# Kontakter.net
KiCad netlist of a schematic drawn in Altium Designer
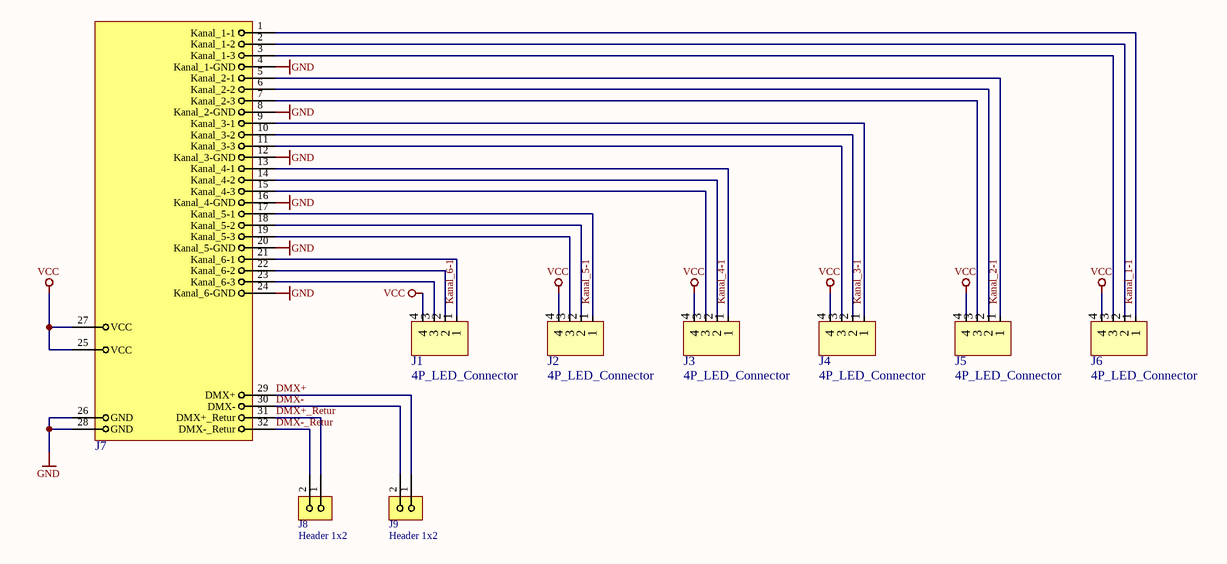
[diagram p0: Kontakter.SchDoc]

(export (version "E")
  (design (tool "Eeschema 10.0.6"))
  (components
    (comp (ref "J1")
      (value "4P_LED_Connector")
      (footprint "LED_solder_connections")
      (libsource (lib "4P_LED_connector") (part "4P_LED_Connector"))
    )
    (comp (ref "J2")
      (value "4P_LED_Connector")
      (footprint "LED_solder_connections")
      (libsource (lib "4P_LED_connector") (part "4P_LED_Connector"))
    )
    (comp (ref "J3")
      (value "4P_LED_Connector")
      (footprint "LED_solder_connections")
      (libsource (lib "4P_LED_connector") (part "4P_LED_Connector"))
    )
    (comp (ref "J4")
      (value "4P_LED_Connector")
      (footprint "LED_solder_connections")
      (libsource (lib "4P_LED_connector") (part "4P_LED_Connector"))
    )
    (comp (ref "J5")
      (value "4P_LED_Connector")
      (footprint "LED_solder_connections")
      (libsource (lib "4P_LED_connector") (part "4P_LED_Connector"))
    )
    (comp (ref "J6")
      (value "4P_LED_Connector")
      (footprint "LED_solder_connections")
      (libsource (lib "4P_LED_connector") (part "4P_LED_Connector"))
    )
    (comp (ref "J7")
      (value "Lysreklameparalellbusskontakt2015")
      (footprint "HDRRA32W64P254_2X16_4064X1260X600B")
      (libsource (lib "Lysreklameparalellbusskontakt2015") (part "Lysreklameparalellbusskontakt2015"))
    )
    (comp (ref "J8")
      (value "Header 1x2")
      (footprint "HDRV2W64P254_1X2_508X254X900B")
      (description "2,54mm pitch")
      (libsource (lib "OVLib") (part "Header1x2"))
    )
    (comp (ref "J9")
      (value "Header 1x2")
      (footprint "HDRV2W64P254_1X2_508X254X900B")
      (description "2,54mm pitch")
      (libsource (lib "OVLib") (part "Header1x2"))
    )
  )
  (nets
    (net (code "1") (name "/DMX+") (class "Default")
      (node (ref "J7") (pin "29") (pinfunction "DMX+_29") (pintype "passive"))
      (node (ref "J9") (pin "1") (pinfunction "1_1") (pintype "passive"))
    )
    (net (code "2") (name "/DMX+_Retur") (class "Default")
      (node (ref "J7") (pin "31") (pinfunction "DMX+_Retur_31") (pintype "passive"))
      (node (ref "J8") (pin "1") (pinfunction "1_1") (pintype "passive"))
    )
    (net (code "3") (name "/DMX-") (class "Default")
      (node (ref "J7") (pin "30") (pinfunction "DMX-_30") (pintype "passive"))
      (node (ref "J9") (pin "2") (pinfunction "2_2") (pintype "passive"))
    )
    (net (code "4") (name "/DMX-_Retur") (class "Default")
      (node (ref "J7") (pin "32") (pinfunction "DMX-_Retur_32") (pintype "passive"))
      (node (ref "J8") (pin "2") (pinfunction "2_2") (pintype "passive"))
    )
    (net (code "5") (name "/Kanal_1-1") (class "Default")
      (node (ref "J6") (pin "1") (pinfunction "1_1") (pintype "passive"))
      (node (ref "J7") (pin "1") (pinfunction "Kanal_1-1_1") (pintype "passive"))
    )
    (net (code "6") (name "/Kanal_2-1") (class "Default")
      (node (ref "J5") (pin "1") (pinfunction "1_1") (pintype "passive"))
      (node (ref "J7") (pin "5") (pinfunction "Kanal_2-1_5") (pintype "passive"))
    )
    (net (code "7") (name "/Kanal_3-1") (class "Default")
      (node (ref "J4") (pin "1") (pinfunction "1_1") (pintype "passive"))
      (node (ref "J7") (pin "9") (pinfunction "Kanal_3-1_9") (pintype "passive"))
    )
    (net (code "8") (name "/Kanal_4-1") (class "Default")
      (node (ref "J3") (pin "1") (pinfunction "1_1") (pintype "passive"))
      (node (ref "J7") (pin "13") (pinfunction "Kanal_4-1_13") (pintype "passive"))
    )
    (net (code "9") (name "/Kanal_5-1") (class "Default")
      (node (ref "J2") (pin "1") (pinfunction "1_1") (pintype "passive"))
      (node (ref "J7") (pin "17") (pinfunction "Kanal_5-1_17") (pintype "passive"))
    )
    (net (code "10") (name "/Kanal_6-1") (class "Default")
      (node (ref "J1") (pin "1") (pinfunction "1_1") (pintype "passive"))
      (node (ref "J7") (pin "21") (pinfunction "Kanal_6-1_21") (pintype "passive"))
    )
    (net (code "11") (name "GND") (class "Default")
      (node (ref "J7") (pin "12") (pinfunction "Kanal_3-GND_12") (pintype "passive"))
      (node (ref "J7") (pin "16") (pinfunction "Kanal_4-GND_16") (pintype "passive"))
      (node (ref "J7") (pin "20") (pinfunction "Kanal_5-GND_20") (pintype "passive"))
      (node (ref "J7") (pin "24") (pinfunction "Kanal_6-GND_24") (pintype "passive"))
      (node (ref "J7") (pin "26") (pinfunction "GND_26") (pintype "passive"))
      (node (ref "J7") (pin "28") (pinfunction "GND_28") (pintype "passive"))
      (node (ref "J7") (pin "4") (pinfunction "Kanal_1-GND_4") (pintype "passive"))
      (node (ref "J7") (pin "8") (pinfunction "Kanal_2-GND_8") (pintype "passive"))
    )
    (net (code "12") (name "Net-(J7-Kanal_1-2)") (class "Default")
      (node (ref "J6") (pin "2") (pinfunction "2_2") (pintype "passive"))
      (node (ref "J7") (pin "2") (pinfunction "Kanal_1-2_2") (pintype "passive"))
    )
    (net (code "13") (name "Net-(J7-Kanal_1-3)") (class "Default")
      (node (ref "J6") (pin "3") (pinfunction "3_3") (pintype "passive"))
      (node (ref "J7") (pin "3") (pinfunction "Kanal_1-3_3") (pintype "passive"))
    )
    (net (code "14") (name "Net-(J7-Kanal_2-2)") (class "Default")
      (node (ref "J5") (pin "2") (pinfunction "2_2") (pintype "passive"))
      (node (ref "J7") (pin "6") (pinfunction "Kanal_2-2_6") (pintype "passive"))
    )
    (net (code "15") (name "Net-(J7-Kanal_2-3)") (class "Default")
      (node (ref "J5") (pin "3") (pinfunction "3_3") (pintype "passive"))
      (node (ref "J7") (pin "7") (pinfunction "Kanal_2-3_7") (pintype "passive"))
    )
    (net (code "16") (name "Net-(J7-Kanal_3-2)") (class "Default")
      (node (ref "J4") (pin "2") (pinfunction "2_2") (pintype "passive"))
      (node (ref "J7") (pin "10") (pinfunction "Kanal_3-2_10") (pintype "passive"))
    )
    (net (code "17") (name "Net-(J7-Kanal_3-3)") (class "Default")
      (node (ref "J4") (pin "3") (pinfunction "3_3") (pintype "passive"))
      (node (ref "J7") (pin "11") (pinfunction "Kanal_3-3_11") (pintype "passive"))
    )
    (net (code "18") (name "Net-(J7-Kanal_4-2)") (class "Default")
      (node (ref "J3") (pin "2") (pinfunction "2_2") (pintype "passive"))
      (node (ref "J7") (pin "14") (pinfunction "Kanal_4-2_14") (pintype "passive"))
    )
    (net (code "19") (name "Net-(J7-Kanal_4-3)") (class "Default")
      (node (ref "J3") (pin "3") (pinfunction "3_3") (pintype "passive"))
      (node (ref "J7") (pin "15") (pinfunction "Kanal_4-3_15") (pintype "passive"))
    )
    (net (code "20") (name "Net-(J7-Kanal_5-2)") (class "Default")
      (node (ref "J2") (pin "2") (pinfunction "2_2") (pintype "passive"))
      (node (ref "J7") (pin "18") (pinfunction "Kanal_5-2_18") (pintype "passive"))
    )
    (net (code "21") (name "Net-(J7-Kanal_5-3)") (class "Default")
      (node (ref "J2") (pin "3") (pinfunction "3_3") (pintype "passive"))
      (node (ref "J7") (pin "19") (pinfunction "Kanal_5-3_19") (pintype "passive"))
    )
    (net (code "22") (name "Net-(J7-Kanal_6-2)") (class "Default")
      (node (ref "J1") (pin "2") (pinfunction "2_2") (pintype "passive"))
      (node (ref "J7") (pin "22") (pinfunction "Kanal_6-2_22") (pintype "passive"))
    )
    (net (code "23") (name "Net-(J7-Kanal_6-3)") (class "Default")
      (node (ref "J1") (pin "3") (pinfunction "3_3") (pintype "passive"))
      (node (ref "J7") (pin "23") (pinfunction "Kanal_6-3_23") (pintype "passive"))
    )
    (net (code "24") (name "VCC") (class "Default")
      (node (ref "J1") (pin "4") (pinfunction "4_4") (pintype "passive"))
      (node (ref "J2") (pin "4") (pinfunction "4_4") (pintype "passive"))
      (node (ref "J3") (pin "4") (pinfunction "4_4") (pintype "passive"))
      (node (ref "J4") (pin "4") (pinfunction "4_4") (pintype "passive"))
      (node (ref "J5") (pin "4") (pinfunction "4_4") (pintype "passive"))
      (node (ref "J6") (pin "4") (pinfunction "4_4") (pintype "passive"))
      (node (ref "J7") (pin "25") (pinfunction "VCC_25") (pintype "passive"))
      (node (ref "J7") (pin "27") (pinfunction "VCC_27") (pintype "passive"))
    )
  )
)
